# SCH_FSR_Amplifier_2023-05-21.net
KiCad netlist of a schematic drawn in EasyEDA
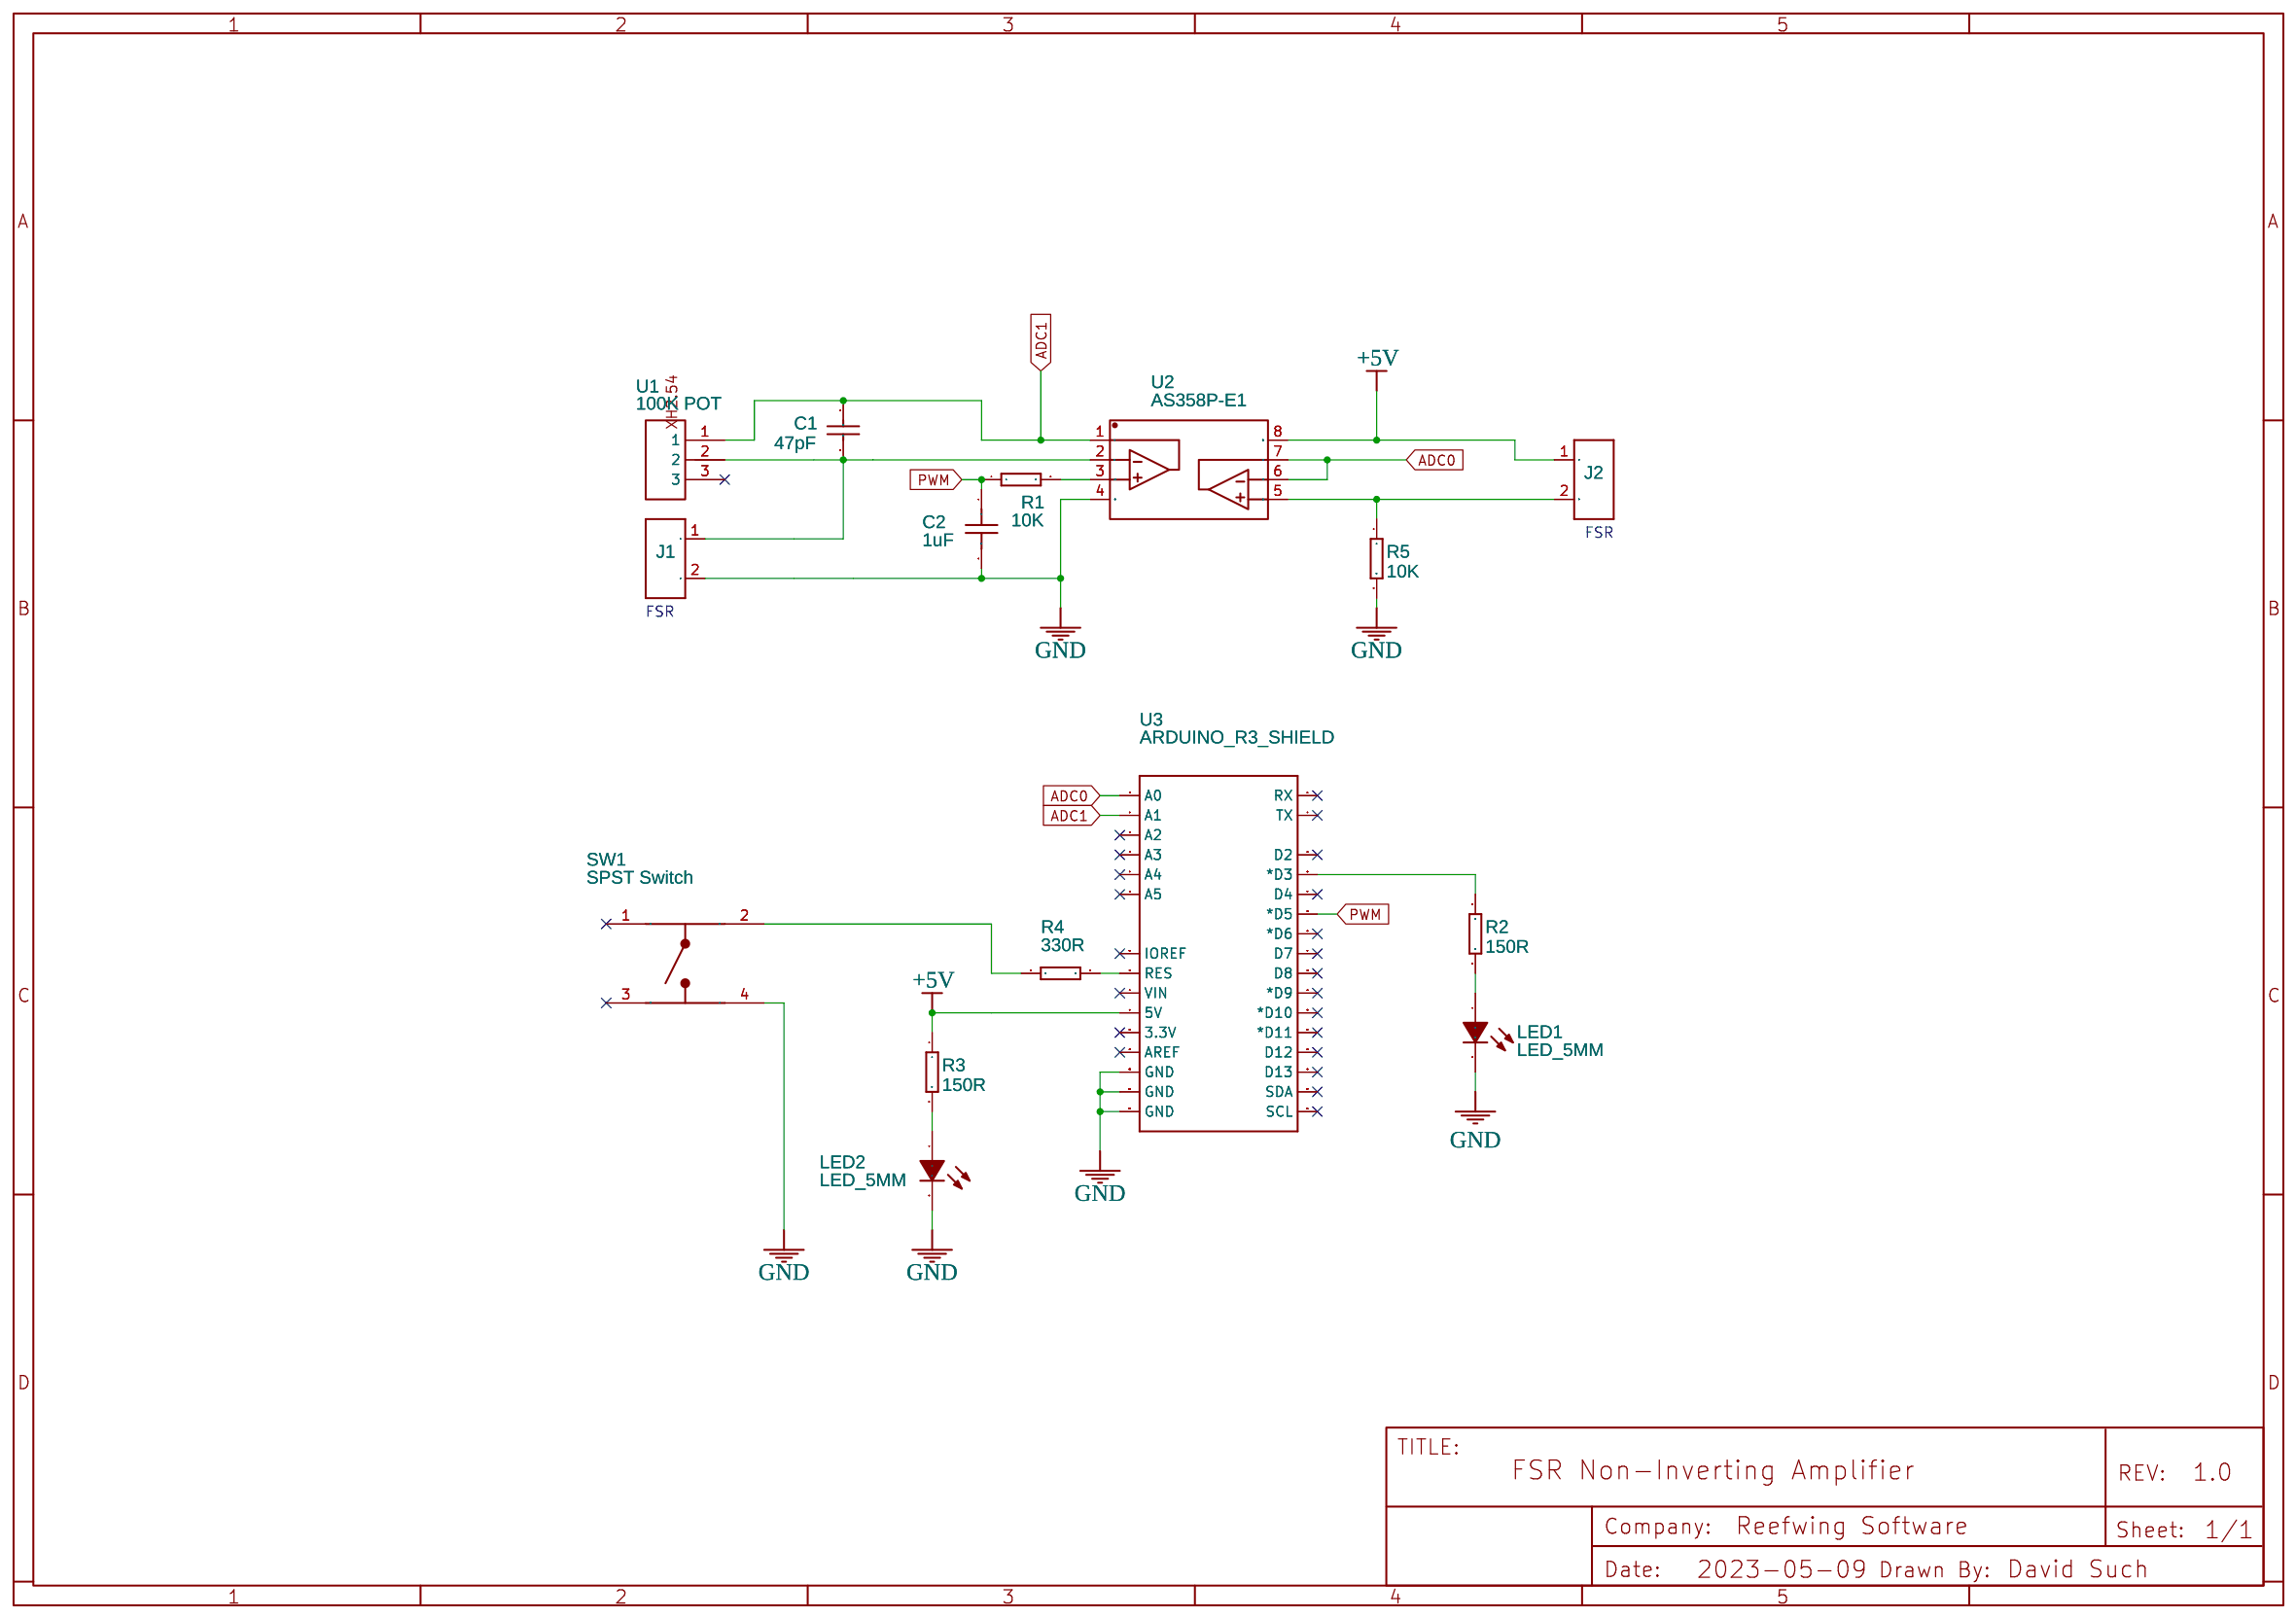
[diagram p0: schematic sheet]

(export (version "E")
  (design (tool "Eeschema 10.0.6"))
  (components
    (comp (ref "C1")
      (value "47pF")
      (fields
        (field (name "BOM_Manufacturer Part") "Ceramic capacitors47PF 3KV")
        (field (name "BOM_Supplier Part") "C19375")
      )
      (libsource (lib "") (part "Ceramic capacitors47PF 3KV"))
    )
    (comp (ref "C2")
      (value "1uF")
      (fields
        (field (name "BOM_Manufacturer Part") "1uf/250V/CBBCapacitor")
        (field (name "BOM_Supplier Part") "C29321")
      )
      (libsource (lib "") (part "1uf/250V/CBBCapacitor"))
    )
    (comp (ref "J1")
      (value "Screw Terminal")
      (fields (field (name "BOM_Manufacturer Part") "?"))
      (libsource (lib "") (part "Screw Terminal"))
    )
    (comp (ref "J2")
      (value "Screw Terminal")
      (fields (field (name "BOM_Manufacturer Part") "?"))
      (libsource (lib "") (part "Screw Terminal_1"))
    )
    (comp (ref "LED1")
      (value "LED_5MM")
      (fields (field (name "BOM_Supplier Part") "C9900023552"))
      (libsource (lib "") (part "LED_5MM"))
    )
    (comp (ref "LED2")
      (value "LED_5MM")
      (fields (field (name "BOM_Supplier Part") "C9900023552"))
      (libsource (lib "") (part "LED_5MM"))
    )
    (comp (ref "R1") (value "10K") (libsource (lib "") (part "RESISTOR_1")))
    (comp (ref "R2") (value "150R") (libsource (lib "") (part "RESISTOR")))
    (comp (ref "R3") (value "150R") (libsource (lib "") (part "RESISTOR")))
    (comp (ref "R4") (value "330R") (libsource (lib "") (part "RESISTOR_1")))
    (comp (ref "R5") (value "10K") (libsource (lib "") (part "RESISTOR")))
    (comp (ref "SW1")
      (value "SPST Switch")
      (fields (field (name "BOM_Manufacturer Part") "TC-12EA") (field (name "BOM_Supplier Part") "SP0609"))
      (libsource (lib "") (part "SPST PCB Mount Tactile Switch Round"))
    )
    (comp (ref "U1")
      (value "100K POT")
      (fields (field (name "BOM_Manufacturer Part") "New SchematicLib"))
      (libsource (lib "") (part "XH2.54_3_PIn_Connector"))
    )
    (comp (ref "U2")
      (value "AS358P-E1")
      (fields (field (name "BOM_Supplier Part") "C69130"))
      (libsource (lib "") (part "AS358P-E1"))
    )
    (comp (ref "U3") (value "ARDUINO_R3_SHIELD") (libsource (lib "") (part "ARDUINO_R3_SHIELD")))
  )
  (nets
    (net (code "1") (name "+5V") (class "Default")
      (node (ref "J2") (pin "1") (pinfunction "1_1") (pintype "unspecified"))
      (node (ref "R3") (pin "1") (pinfunction "1_1") (pintype "unspecified"))
      (node (ref "U2") (pin "8") (pinfunction "+VS_8") (pintype "unspecified"))
      (node (ref "U3") (pin "5V") (pinfunction "5V_5V") (pintype "unspecified"))
    )
    (net (code "2") (name "ADC0") (class "Default")
      (node (ref "U2") (pin "6") (pinfunction "6_6") (pintype "unspecified"))
      (node (ref "U2") (pin "7") (pinfunction "7_7") (pintype "unspecified"))
      (node (ref "U3") (pin "A0") (pinfunction "A0_A0") (pintype "unspecified"))
    )
    (net (code "3") (name "ADC1") (class "Default")
      (node (ref "C1") (pin "1") (pinfunction "1_1") (pintype "input"))
      (node (ref "U1") (pin "1") (pinfunction "1_1") (pintype "unspecified"))
      (node (ref "U2") (pin "1") (pinfunction "1_1") (pintype "unspecified"))
      (node (ref "U3") (pin "A1") (pinfunction "A1_A1") (pintype "unspecified"))
    )
    (net (code "4") (name "GND") (class "Default")
      (node (ref "C2") (pin "2") (pinfunction "2_2") (pintype "unspecified"))
      (node (ref "J1") (pin "2") (pinfunction "2_2") (pintype "unspecified"))
      (node (ref "LED1") (pin "2") (pinfunction "K_2") (pintype "input"))
      (node (ref "LED2") (pin "2") (pinfunction "K_2") (pintype "input"))
      (node (ref "R5") (pin "2") (pinfunction "2_2") (pintype "unspecified"))
      (node (ref "SW1") (pin "4") (pinfunction "4_4") (pintype "unspecified"))
      (node (ref "U2") (pin "4") (pinfunction "-VS_4") (pintype "unspecified"))
      (node (ref "U3") (pin "GND@0") (pinfunction "GND_GND@0") (pintype "unspecified"))
      (node (ref "U3") (pin "GND@1") (pinfunction "GND_GND@1") (pintype "unspecified"))
      (node (ref "U3") (pin "GND@2") (pinfunction "GND_GND@2") (pintype "unspecified"))
    )
    (net (code "5") (name "Net-(C1-Pad2)") (class "Default")
      (node (ref "C1") (pin "2") (pinfunction "2_2") (pintype "input"))
      (node (ref "J1") (pin "1") (pinfunction "1_1") (pintype "unspecified"))
      (node (ref "U1") (pin "2") (pinfunction "2_2") (pintype "unspecified"))
      (node (ref "U2") (pin "2") (pinfunction "2_2") (pintype "unspecified"))
    )
    (net (code "6") (name "Net-(J2-Pad2)") (class "Default")
      (node (ref "J2") (pin "2") (pinfunction "2_2") (pintype "unspecified"))
      (node (ref "R5") (pin "1") (pinfunction "1_1") (pintype "unspecified"))
      (node (ref "U2") (pin "5") (pinfunction "5_5") (pintype "unspecified"))
    )
    (net (code "7") (name "Net-(LED1-A)") (class "Default")
      (node (ref "LED1") (pin "1") (pinfunction "A_1") (pintype "input"))
      (node (ref "R2") (pin "2") (pinfunction "2_2") (pintype "unspecified"))
    )
    (net (code "8") (name "Net-(LED2-A)") (class "Default")
      (node (ref "LED2") (pin "1") (pinfunction "A_1") (pintype "input"))
      (node (ref "R3") (pin "2") (pinfunction "2_2") (pintype "unspecified"))
    )
    (net (code "9") (name "Net-(R4-Pad1)") (class "Default")
      (node (ref "R4") (pin "1") (pinfunction "1_1") (pintype "unspecified"))
      (node (ref "SW1") (pin "2") (pinfunction "2_2") (pintype "unspecified"))
    )
    (net (code "10") (name "Net-(R4-Pad2)") (class "Default")
      (node (ref "R4") (pin "2") (pinfunction "2_2") (pintype "unspecified"))
      (node (ref "U3") (pin "RES") (pinfunction "RES_RES") (pintype "unspecified"))
    )
    (net (code "11") (name "Net-(U2-VDD)") (class "Default")
      (node (ref "R1") (pin "2") (pinfunction "2_2") (pintype "unspecified"))
      (node (ref "U2") (pin "3") (pinfunction "VDD_3") (pintype "unspecified"))
    )
    (net (code "12") (name "Net-(U3-*D3)") (class "Default")
      (node (ref "R2") (pin "1") (pinfunction "1_1") (pintype "unspecified"))
      (node (ref "U3") (pin "D3") (pinfunction "*D3_D3") (pintype "unspecified"))
    )
    (net (code "13") (name "PWM") (class "Default")
      (node (ref "C2") (pin "1") (pinfunction "1_1") (pintype "unspecified"))
      (node (ref "R1") (pin "1") (pinfunction "1_1") (pintype "unspecified"))
      (node (ref "U3") (pin "D5") (pinfunction "*D5_D5") (pintype "unspecified"))
    )
    (net (code "14") (name "unconnected-(SW1-Pad1)") (class "Default")
      (node (ref "SW1") (pin "1") (pinfunction "1_1") (pintype "unspecified+no_connect"))
    )
    (net (code "15") (name "unconnected-(SW1-Pad3)") (class "Default")
      (node (ref "SW1") (pin "3") (pinfunction "3_3") (pintype "unspecified+no_connect"))
    )
    (net (code "16") (name "unconnected-(U1-Pad3)") (class "Default")
      (node (ref "U1") (pin "3") (pinfunction "3_3") (pintype "unspecified+no_connect"))
    )
    (net (code "17") (name "unconnected-(U3-*D6-PadD6)") (class "Default")
      (node (ref "U3") (pin "D6") (pinfunction "*D6_D6") (pintype "unspecified+no_connect"))
    )
    (net (code "18") (name "unconnected-(U3-*D9-PadD9)") (class "Default")
      (node (ref "U3") (pin "D9") (pinfunction "*D9_D9") (pintype "unspecified+no_connect"))
    )
    (net (code "19") (name "unconnected-(U3-*D10-PadD10)") (class "Default")
      (node (ref "U3") (pin "D10") (pinfunction "*D10_D10") (pintype "unspecified+no_connect"))
    )
    (net (code "20") (name "unconnected-(U3-*D11-PadD11)") (class "Default")
      (node (ref "U3") (pin "D11") (pinfunction "*D11_D11") (pintype "unspecified+no_connect"))
    )
    (net (code "21") (name "unconnected-(U3-Pad3.3V)") (class "Default")
      (node (ref "U3") (pin "3.3V") (pinfunction "3.3V_3.3V") (pintype "unspecified+no_connect"))
    )
    (net (code "22") (name "unconnected-(U3-PadA2)") (class "Default")
      (node (ref "U3") (pin "A2") (pinfunction "A2_A2") (pintype "unspecified+no_connect"))
    )
    (net (code "23") (name "unconnected-(U3-PadA3)") (class "Default")
      (node (ref "U3") (pin "A3") (pinfunction "A3_A3") (pintype "unspecified+no_connect"))
    )
    (net (code "24") (name "unconnected-(U3-PadA4)") (class "Default")
      (node (ref "U3") (pin "A4") (pinfunction "A4_A4") (pintype "unspecified+no_connect"))
    )
    (net (code "25") (name "unconnected-(U3-PadA5)") (class "Default")
      (node (ref "U3") (pin "A5") (pinfunction "A5_A5") (pintype "unspecified+no_connect"))
    )
    (net (code "26") (name "unconnected-(U3-PadAREF)") (class "Default")
      (node (ref "U3") (pin "AREF") (pinfunction "AREF_AREF") (pintype "unspecified+no_connect"))
    )
    (net (code "27") (name "unconnected-(U3-PadD2)") (class "Default")
      (node (ref "U3") (pin "D2") (pinfunction "D2_D2") (pintype "unspecified+no_connect"))
    )
    (net (code "28") (name "unconnected-(U3-PadD4)") (class "Default")
      (node (ref "U3") (pin "D4") (pinfunction "D4_D4") (pintype "unspecified+no_connect"))
    )
    (net (code "29") (name "unconnected-(U3-PadD7)") (class "Default")
      (node (ref "U3") (pin "D7") (pinfunction "D7_D7") (pintype "unspecified+no_connect"))
    )
    (net (code "30") (name "unconnected-(U3-PadD8)") (class "Default")
      (node (ref "U3") (pin "D8") (pinfunction "D8_D8") (pintype "unspecified+no_connect"))
    )
    (net (code "31") (name "unconnected-(U3-PadD12)") (class "Default")
      (node (ref "U3") (pin "D12") (pinfunction "D12_D12") (pintype "unspecified+no_connect"))
    )
    (net (code "32") (name "unconnected-(U3-PadD13)") (class "Default")
      (node (ref "U3") (pin "D13") (pinfunction "D13_D13") (pintype "unspecified+no_connect"))
    )
    (net (code "33") (name "unconnected-(U3-PadIOREF)") (class "Default")
      (node (ref "U3") (pin "IOREF") (pinfunction "IOREF_IOREF") (pintype "unspecified+no_connect"))
    )
    (net (code "34") (name "unconnected-(U3-PadRX)") (class "Default")
      (node (ref "U3") (pin "RX") (pinfunction "RX_RX") (pintype "unspecified+no_connect"))
    )
    (net (code "35") (name "unconnected-(U3-PadSCL)") (class "Default")
      (node (ref "U3") (pin "SCL") (pinfunction "SCL_SCL") (pintype "unspecified+no_connect"))
    )
    (net (code "36") (name "unconnected-(U3-PadSDA)") (class "Default")
      (node (ref "U3") (pin "SDA") (pinfunction "SDA_SDA") (pintype "unspecified+no_connect"))
    )
    (net (code "37") (name "unconnected-(U3-PadTX)") (class "Default")
      (node (ref "U3") (pin "TX") (pinfunction "TX_TX") (pintype "unspecified+no_connect"))
    )
    (net (code "38") (name "unconnected-(U3-PadVIN)") (class "Default")
      (node (ref "U3") (pin "VIN") (pinfunction "VIN_VIN") (pintype "unspecified+no_connect"))
    )
  )
)
